# easyeda.net
KiCad netlist of a schematic drawn in EasyEDA
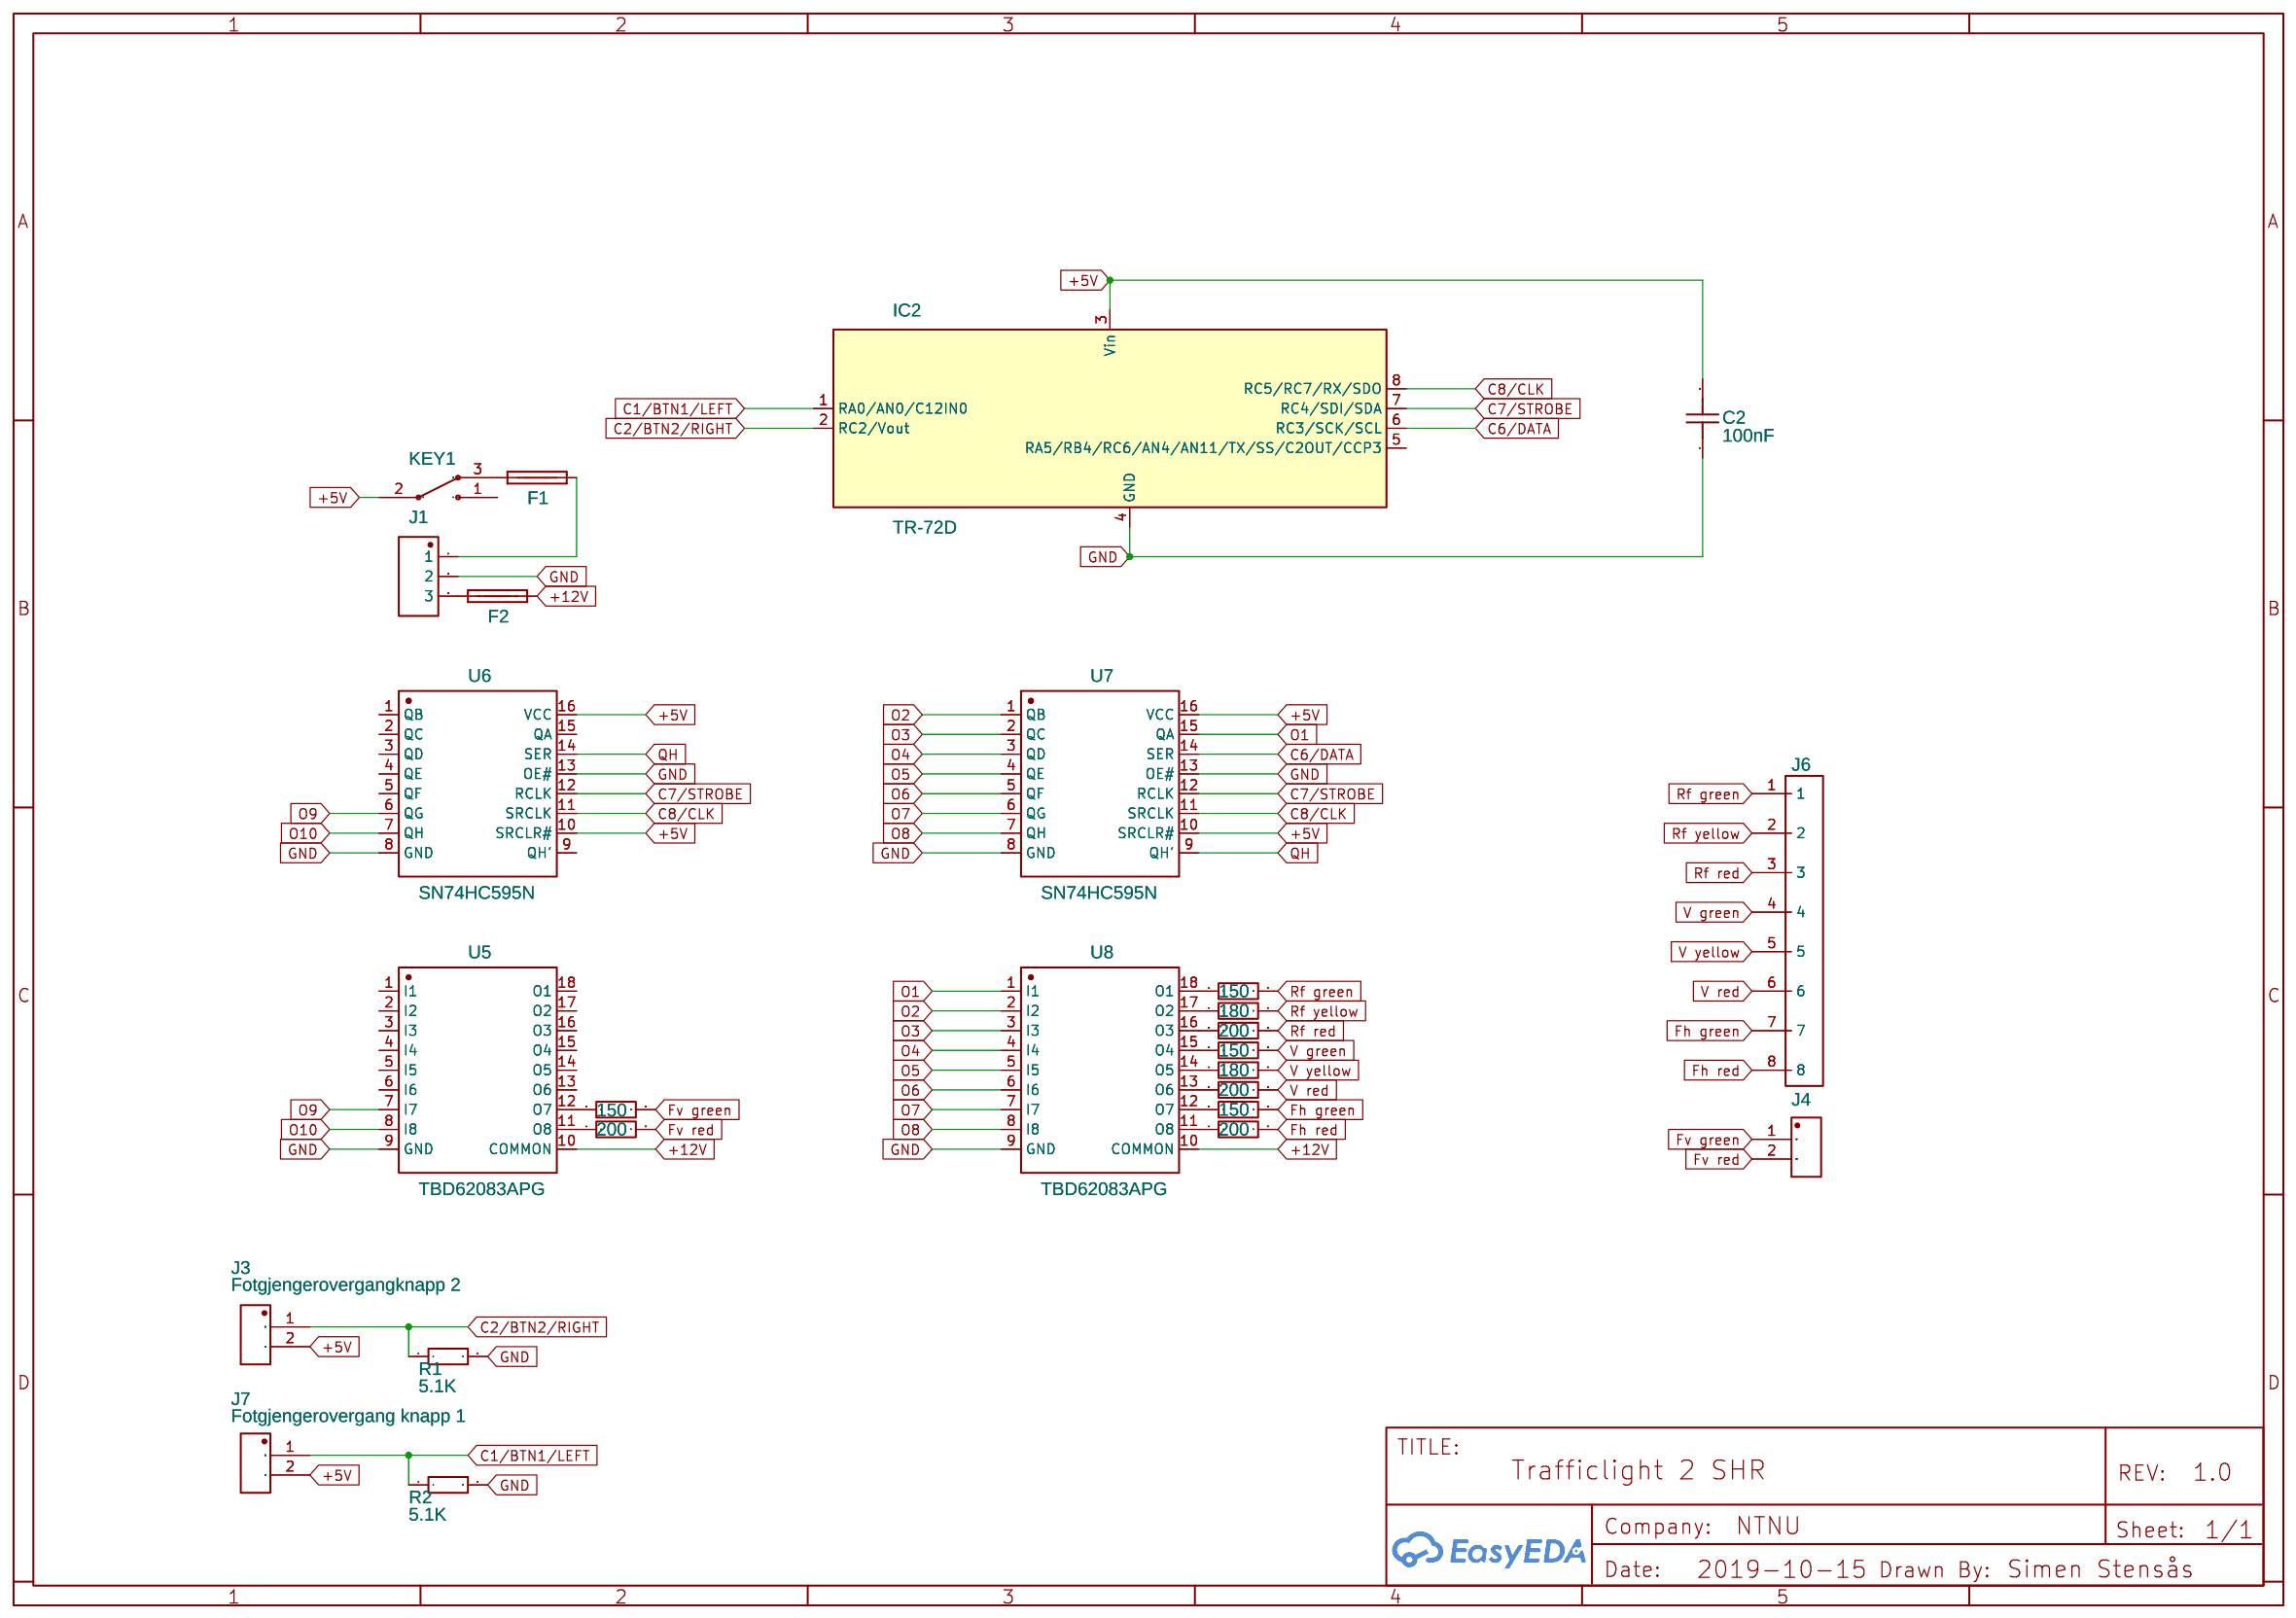
[diagram p0: schematic sheet]

(export (version "E")
  (design (tool "Eeschema 10.0.6"))
  (components
    (comp (ref "C2")
      (value "100nF")
      (fields
        (field (name "BOM_Manufacturer Part") "1210B106K100CT")
        (field (name "BOM_Supplier Part") "C304011")
      )
      (libsource (lib "") (part "1210B106K100CT"))
    )
    (comp (ref "F1")
      (value "NO")
      (fields
        (field (name "BOM_Manufacturer Part") "3403.0015.11")
        (field (name "BOM_Supplier Part") "693-3403.0015.11")
      )
      (libsource (lib "") (part "Unknown_270_225"))
    )
    (comp (ref "F2")
      (value "NO")
      (fields
        (field (name "BOM_Manufacturer Part") "3403.0015.11")
        (field (name "BOM_Supplier Part") "693-3403.0015.11")
      )
      (libsource (lib "") (part "Unknown_250_285"))
    )
    (comp (ref "IC2") (value "TR-72D") (libsource (lib "") (part "Unknown_415_200")))
    (comp (ref "J1") (value "KF127_3P_5.08") (libsource (lib "") (part "Unknown_205_285")))
    (comp (ref "J3")
      (value "Fotgjengerovergangknapp 2")
      (fields (field (name "BOM_Manufacturer Part") "KF127L-5.08"))
      (libsource (lib "") (part "Unknown_135_670"))
    )
    (comp (ref "J4")
      (value "KF127_2P_5.08")
      (fields (field (name "BOM_Manufacturer Part") "KF127L-5.08"))
      (libsource (lib "") (part "Unknown_895_575"))
    )
    (comp (ref "J6") (value "KF127-8P") (libsource (lib "") (part "Unknown_900_455")))
    (comp (ref "J7")
      (value "Fotgjengerovergang knapp 1")
      (fields (field (name "BOM_Manufacturer Part") "KF127L-5.08"))
      (libsource (lib "") (part "Unknown_135_735"))
    )
    (comp (ref "KEY1")
      (value "MSK-11027 Toggle Switches")
      (fields (field (name "BOM_Supplier Part") "C21381"))
      (libsource (lib "") (part "Unknown_215_235"))
    )
    (comp (ref "R1")
      (value "5.1K")
      (fields
        (field (name "BOM_Manufacturer Part") "RMC12065.1K1%N")
        (field (name "BOM_Supplier Part") "C325932")
      )
      (libsource (lib "") (part "RMC12065.1K1%N"))
    )
    (comp (ref "R2")
      (value "5.1K")
      (fields
        (field (name "BOM_Manufacturer Part") "RMC12065.1K1%N")
        (field (name "BOM_Supplier Part") "C325932")
      )
      (libsource (lib "") (part "RMC12065.1K1%N"))
    )
    (comp (ref "R3")
      (value "150")
      (fields
        (field (name "BOM_Manufacturer Part") "RC1206JR-07160RL")
        (field (name "BOM_Supplier Part") "C137196")
      )
      (libsource (lib "") (part "RC1206JR-07160RL"))
    )
    (comp (ref "R4")
      (value "200")
      (fields
        (field (name "BOM_Manufacturer Part") "QR1206J200RP05")
        (field (name "BOM_Supplier Part") "C149886")
      )
      (libsource (lib "") (part "QR1206J200RP05"))
    )
    (comp (ref "R5")
      (value "200")
      (fields
        (field (name "BOM_Manufacturer Part") "QR1206J200RP05")
        (field (name "BOM_Supplier Part") "C149886")
      )
      (libsource (lib "") (part "QR1206J200RP05"))
    )
    (comp (ref "R6")
      (value "200")
      (fields
        (field (name "BOM_Manufacturer Part") "QR1206J200RP05")
        (field (name "BOM_Supplier Part") "C149886")
      )
      (libsource (lib "") (part "QR1206J200RP05"))
    )
    (comp (ref "R7")
      (value "200")
      (fields
        (field (name "BOM_Manufacturer Part") "QR1206J200RP05")
        (field (name "BOM_Supplier Part") "C149886")
      )
      (libsource (lib "") (part "QR1206J200RP05"))
    )
    (comp (ref "R16")
      (value "180")
      (fields
        (field (name "BOM_Manufacturer Part") "CR1206-FX-1800ELF")
        (field (name "BOM_Supplier Part") "C204708")
      )
      (libsource (lib "") (part "CR1206-FX-1800ELF"))
    )
    (comp (ref "R17")
      (value "180")
      (fields
        (field (name "BOM_Manufacturer Part") "CR1206-FX-1800ELF")
        (field (name "BOM_Supplier Part") "C204708")
      )
      (libsource (lib "") (part "CR1206-FX-1800ELF"))
    )
    (comp (ref "R18")
      (value "150")
      (fields
        (field (name "BOM_Manufacturer Part") "RC1206JR-07160RL")
        (field (name "BOM_Supplier Part") "C137196")
      )
      (libsource (lib "") (part "RC1206JR-07160RL"))
    )
    (comp (ref "R19")
      (value "150")
      (fields
        (field (name "BOM_Manufacturer Part") "RC1206JR-07160RL")
        (field (name "BOM_Supplier Part") "C137196")
      )
      (libsource (lib "") (part "RC1206JR-07160RL"))
    )
    (comp (ref "R20")
      (value "150")
      (fields
        (field (name "BOM_Manufacturer Part") "RC1206JR-07160RL")
        (field (name "BOM_Supplier Part") "C137196")
      )
      (libsource (lib "") (part "RC1206JR-07160RL"))
    )
    (comp (ref "U5")
      (value "TBD62083APG")
      (fields (field (name "BOM_Supplier Part") "C114143"))
      (libsource (lib "") (part "Unknown_235_535"))
    )
    (comp (ref "U6")
      (value "SN74HC595N")
      (fields (field (name "BOM_Supplier Part") "C78711"))
      (libsource (lib "") (part "Unknown_235_390"))
    )
    (comp (ref "U7")
      (value "SN74HC595N")
      (fields (field (name "BOM_Supplier Part") "C78711"))
      (libsource (lib "") (part "Unknown_550_390"))
    )
    (comp (ref "U8")
      (value "TBD62083APG")
      (fields (field (name "BOM_Supplier Part") "C114143"))
      (libsource (lib "") (part "Unknown_550_535"))
    )
  )
  (nets
    (net (code "1") (name "+5V") (class "Default")
      (node (ref "C2") (pin "2") (pinfunction "2_2") (pintype "unspecified"))
      (node (ref "IC2") (pin "3") (pinfunction "Vin_3") (pintype "bidirectional"))
      (node (ref "J3") (pin "2") (pinfunction "PIN2_2") (pintype "unspecified"))
      (node (ref "J7") (pin "2") (pinfunction "PIN2_2") (pintype "unspecified"))
      (node (ref "KEY1") (pin "2") (pinfunction "2_2") (pintype "unspecified"))
      (node (ref "U6") (pin "10") (pinfunction "SRCLR#_10") (pintype "unspecified"))
      (node (ref "U6") (pin "16") (pinfunction "VCC_16") (pintype "unspecified"))
      (node (ref "U7") (pin "10") (pinfunction "SRCLR#_10") (pintype "unspecified"))
      (node (ref "U7") (pin "16") (pinfunction "VCC_16") (pintype "unspecified"))
    )
    (net (code "2") (name "+12V") (class "Default")
      (node (ref "F2") (pin "2") (pinfunction "2_2") (pintype "bidirectional"))
      (node (ref "U5") (pin "10") (pinfunction "COMMON_10") (pintype "unspecified"))
      (node (ref "U8") (pin "10") (pinfunction "COMMON_10") (pintype "unspecified"))
    )
    (net (code "3") (name "C1{slash}BTN1{slash}LEFT") (class "Default")
      (node (ref "IC2") (pin "1") (pinfunction "RA0/AN0/C12IN0_1") (pintype "bidirectional"))
      (node (ref "J7") (pin "1") (pinfunction "PIN1_1") (pintype "unspecified"))
      (node (ref "R2") (pin "1") (pinfunction "1_1") (pintype "unspecified"))
    )
    (net (code "4") (name "C2{slash}BTN2{slash}RIGHT") (class "Default")
      (node (ref "IC2") (pin "2") (pinfunction "RC2/Vout_2") (pintype "bidirectional"))
      (node (ref "J3") (pin "1") (pinfunction "PIN1_1") (pintype "unspecified"))
      (node (ref "R1") (pin "1") (pinfunction "1_1") (pintype "unspecified"))
    )
    (net (code "5") (name "C6{slash}DATA") (class "Default")
      (node (ref "IC2") (pin "6") (pinfunction "RC3/SCK/SCL_6") (pintype "bidirectional"))
      (node (ref "U7") (pin "14") (pinfunction "SER_14") (pintype "unspecified"))
    )
    (net (code "6") (name "C7{slash}STROBE") (class "Default")
      (node (ref "IC2") (pin "7") (pinfunction "RC4/SDI/SDA_7") (pintype "bidirectional"))
      (node (ref "U6") (pin "12") (pinfunction "RCLK_12") (pintype "unspecified"))
      (node (ref "U7") (pin "12") (pinfunction "RCLK_12") (pintype "unspecified"))
    )
    (net (code "7") (name "C8{slash}CLK") (class "Default")
      (node (ref "IC2") (pin "8") (pinfunction "RC5/RC7/RX/SDO_8") (pintype "bidirectional"))
      (node (ref "U6") (pin "11") (pinfunction "SRCLK_11") (pintype "unspecified"))
      (node (ref "U7") (pin "11") (pinfunction "SRCLK_11") (pintype "unspecified"))
    )
    (net (code "8") (name "Fh green") (class "Default")
      (node (ref "J6") (pin "7") (pinfunction "7_7") (pintype "unspecified"))
      (node (ref "R18") (pin "2") (pinfunction "2_2") (pintype "input"))
    )
    (net (code "9") (name "Fh red") (class "Default")
      (node (ref "J6") (pin "8") (pinfunction "8_8") (pintype "unspecified"))
      (node (ref "R5") (pin "2") (pinfunction "2_2") (pintype "unspecified"))
    )
    (net (code "10") (name "Fv green") (class "Default")
      (node (ref "J4") (pin "1") (pinfunction "PIN1_1") (pintype "unspecified"))
      (node (ref "R3") (pin "2") (pinfunction "2_2") (pintype "input"))
    )
    (net (code "11") (name "Fv red") (class "Default")
      (node (ref "J4") (pin "2") (pinfunction "PIN2_2") (pintype "unspecified"))
      (node (ref "R4") (pin "2") (pinfunction "2_2") (pintype "unspecified"))
    )
    (net (code "12") (name "GND") (class "Default")
      (node (ref "C2") (pin "1") (pinfunction "1_1") (pintype "unspecified"))
      (node (ref "IC2") (pin "4") (pinfunction "GND_4") (pintype "bidirectional"))
      (node (ref "J1") (pin "2") (pinfunction "2_2") (pintype "input"))
      (node (ref "R1") (pin "2") (pinfunction "2_2") (pintype "unspecified"))
      (node (ref "R2") (pin "2") (pinfunction "2_2") (pintype "unspecified"))
      (node (ref "U5") (pin "9") (pinfunction "GND_9") (pintype "unspecified"))
      (node (ref "U6") (pin "13") (pinfunction "OE#_13") (pintype "unspecified"))
      (node (ref "U6") (pin "8") (pinfunction "GND_8") (pintype "unspecified"))
      (node (ref "U7") (pin "13") (pinfunction "OE#_13") (pintype "unspecified"))
      (node (ref "U7") (pin "8") (pinfunction "GND_8") (pintype "unspecified"))
      (node (ref "U8") (pin "9") (pinfunction "GND_9") (pintype "unspecified"))
    )
    (net (code "13") (name "Net-(F1-Pad1)") (class "Default")
      (node (ref "F1") (pin "1") (pinfunction "1_1") (pintype "bidirectional"))
      (node (ref "KEY1") (pin "3") (pinfunction "3_3") (pintype "unspecified"))
    )
    (net (code "14") (name "Net-(F1-Pad2)") (class "Default")
      (node (ref "F1") (pin "2") (pinfunction "2_2") (pintype "bidirectional"))
      (node (ref "J1") (pin "1") (pinfunction "1_1") (pintype "input"))
    )
    (net (code "15") (name "Net-(F2-Pad1)") (class "Default")
      (node (ref "F2") (pin "1") (pinfunction "1_1") (pintype "bidirectional"))
      (node (ref "J1") (pin "3") (pinfunction "3_3") (pintype "input"))
    )
    (net (code "16") (name "Net-(U5-O7)") (class "Default")
      (node (ref "R3") (pin "1") (pinfunction "1_1") (pintype "input"))
      (node (ref "U5") (pin "12") (pinfunction "O7_12") (pintype "unspecified"))
    )
    (net (code "17") (name "Net-(U5-O8)") (class "Default")
      (node (ref "R4") (pin "1") (pinfunction "1_1") (pintype "unspecified"))
      (node (ref "U5") (pin "11") (pinfunction "O8_11") (pintype "unspecified"))
    )
    (net (code "18") (name "Net-(U8-O1)") (class "Default")
      (node (ref "R20") (pin "1") (pinfunction "1_1") (pintype "input"))
      (node (ref "U8") (pin "18") (pinfunction "O1_18") (pintype "unspecified"))
    )
    (net (code "19") (name "Net-(U8-O2)") (class "Default")
      (node (ref "R17") (pin "1") (pinfunction "1_1") (pintype "unspecified"))
      (node (ref "U8") (pin "17") (pinfunction "O2_17") (pintype "unspecified"))
    )
    (net (code "20") (name "Net-(U8-O3)") (class "Default")
      (node (ref "R7") (pin "1") (pinfunction "1_1") (pintype "unspecified"))
      (node (ref "U8") (pin "16") (pinfunction "O3_16") (pintype "unspecified"))
    )
    (net (code "21") (name "Net-(U8-O4)") (class "Default")
      (node (ref "R19") (pin "1") (pinfunction "1_1") (pintype "input"))
      (node (ref "U8") (pin "15") (pinfunction "O4_15") (pintype "unspecified"))
    )
    (net (code "22") (name "Net-(U8-O5)") (class "Default")
      (node (ref "R16") (pin "1") (pinfunction "1_1") (pintype "unspecified"))
      (node (ref "U8") (pin "14") (pinfunction "O5_14") (pintype "unspecified"))
    )
    (net (code "23") (name "Net-(U8-O6)") (class "Default")
      (node (ref "R6") (pin "1") (pinfunction "1_1") (pintype "unspecified"))
      (node (ref "U8") (pin "13") (pinfunction "O6_13") (pintype "unspecified"))
    )
    (net (code "24") (name "Net-(U8-O7)") (class "Default")
      (node (ref "R18") (pin "1") (pinfunction "1_1") (pintype "input"))
      (node (ref "U8") (pin "12") (pinfunction "O7_12") (pintype "unspecified"))
    )
    (net (code "25") (name "Net-(U8-O8)") (class "Default")
      (node (ref "R5") (pin "1") (pinfunction "1_1") (pintype "unspecified"))
      (node (ref "U8") (pin "11") (pinfunction "O8_11") (pintype "unspecified"))
    )
    (net (code "26") (name "O1") (class "Default")
      (node (ref "U7") (pin "15") (pinfunction "QA_15") (pintype "unspecified"))
      (node (ref "U8") (pin "1") (pinfunction "I1_1") (pintype "unspecified"))
    )
    (net (code "27") (name "O2") (class "Default")
      (node (ref "U7") (pin "1") (pinfunction "QB_1") (pintype "unspecified"))
      (node (ref "U8") (pin "2") (pinfunction "I2_2") (pintype "unspecified"))
    )
    (net (code "28") (name "O3") (class "Default")
      (node (ref "U7") (pin "2") (pinfunction "QC_2") (pintype "unspecified"))
      (node (ref "U8") (pin "3") (pinfunction "I3_3") (pintype "unspecified"))
    )
    (net (code "29") (name "O4") (class "Default")
      (node (ref "U7") (pin "3") (pinfunction "QD_3") (pintype "unspecified"))
      (node (ref "U8") (pin "4") (pinfunction "I4_4") (pintype "unspecified"))
    )
    (net (code "30") (name "O5") (class "Default")
      (node (ref "U7") (pin "4") (pinfunction "QE_4") (pintype "unspecified"))
      (node (ref "U8") (pin "5") (pinfunction "I5_5") (pintype "unspecified"))
    )
    (net (code "31") (name "O6") (class "Default")
      (node (ref "U7") (pin "5") (pinfunction "QF_5") (pintype "unspecified"))
      (node (ref "U8") (pin "6") (pinfunction "I6_6") (pintype "unspecified"))
    )
    (net (code "32") (name "O7") (class "Default")
      (node (ref "U7") (pin "6") (pinfunction "QG_6") (pintype "unspecified"))
      (node (ref "U8") (pin "7") (pinfunction "I7_7") (pintype "unspecified"))
    )
    (net (code "33") (name "O8") (class "Default")
      (node (ref "U7") (pin "7") (pinfunction "QH_7") (pintype "unspecified"))
      (node (ref "U8") (pin "8") (pinfunction "I8_8") (pintype "unspecified"))
    )
    (net (code "34") (name "O9") (class "Default")
      (node (ref "U5") (pin "7") (pinfunction "I7_7") (pintype "unspecified"))
      (node (ref "U6") (pin "6") (pinfunction "QG_6") (pintype "unspecified"))
    )
    (net (code "35") (name "O10") (class "Default")
      (node (ref "U5") (pin "8") (pinfunction "I8_8") (pintype "unspecified"))
      (node (ref "U6") (pin "7") (pinfunction "QH_7") (pintype "unspecified"))
    )
    (net (code "36") (name "QH") (class "Default")
      (node (ref "U6") (pin "14") (pinfunction "SER_14") (pintype "unspecified"))
      (node (ref "U7") (pin "9") (pinfunction "QH'_9") (pintype "unspecified"))
    )
    (net (code "37") (name "Rf green") (class "Default")
      (node (ref "J6") (pin "1") (pinfunction "1_1") (pintype "unspecified"))
      (node (ref "R20") (pin "2") (pinfunction "2_2") (pintype "input"))
    )
    (net (code "38") (name "Rf red") (class "Default")
      (node (ref "J6") (pin "3") (pinfunction "3_3") (pintype "unspecified"))
      (node (ref "R7") (pin "2") (pinfunction "2_2") (pintype "unspecified"))
    )
    (net (code "39") (name "Rf yellow") (class "Default")
      (node (ref "J6") (pin "2") (pinfunction "2_2") (pintype "unspecified"))
      (node (ref "R17") (pin "2") (pinfunction "2_2") (pintype "unspecified"))
    )
    (net (code "40") (name "V green") (class "Default")
      (node (ref "J6") (pin "4") (pinfunction "4_4") (pintype "unspecified"))
      (node (ref "R19") (pin "2") (pinfunction "2_2") (pintype "input"))
    )
    (net (code "41") (name "V red") (class "Default")
      (node (ref "J6") (pin "6") (pinfunction "6_6") (pintype "unspecified"))
      (node (ref "R6") (pin "2") (pinfunction "2_2") (pintype "unspecified"))
    )
    (net (code "42") (name "V yellow") (class "Default")
      (node (ref "J6") (pin "5") (pinfunction "5_5") (pintype "unspecified"))
      (node (ref "R16") (pin "2") (pinfunction "2_2") (pintype "unspecified"))
    )
    (net (code "43") (name "unconnected-(IC2-RA5{slash}RB4{slash}RC6{slash}AN4{slash}AN11{slash}TX{slash}SS{slash}C2OUT{slash}CCP3-Pad5)") (class "Default")
      (node (ref "IC2") (pin "5") (pinfunction "RA5/RB4/RC6/AN4/AN11/TX/SS/C2OUT/CCP3_5") (pintype "bidirectional"))
    )
    (net (code "44") (name "unconnected-(KEY1-Pad1)") (class "Default")
      (node (ref "KEY1") (pin "1") (pinfunction "1_1") (pintype "unspecified"))
    )
    (net (code "45") (name "unconnected-(U5-I1-Pad1)") (class "Default")
      (node (ref "U5") (pin "1") (pinfunction "I1_1") (pintype "unspecified"))
    )
    (net (code "46") (name "unconnected-(U5-I2-Pad2)") (class "Default")
      (node (ref "U5") (pin "2") (pinfunction "I2_2") (pintype "unspecified"))
    )
    (net (code "47") (name "unconnected-(U5-I3-Pad3)") (class "Default")
      (node (ref "U5") (pin "3") (pinfunction "I3_3") (pintype "unspecified"))
    )
    (net (code "48") (name "unconnected-(U5-I4-Pad4)") (class "Default")
      (node (ref "U5") (pin "4") (pinfunction "I4_4") (pintype "unspecified"))
    )
    (net (code "49") (name "unconnected-(U5-I5-Pad5)") (class "Default")
      (node (ref "U5") (pin "5") (pinfunction "I5_5") (pintype "unspecified"))
    )
    (net (code "50") (name "unconnected-(U5-I6-Pad6)") (class "Default")
      (node (ref "U5") (pin "6") (pinfunction "I6_6") (pintype "unspecified"))
    )
    (net (code "51") (name "unconnected-(U5-O1-Pad18)") (class "Default")
      (node (ref "U5") (pin "18") (pinfunction "O1_18") (pintype "unspecified"))
    )
    (net (code "52") (name "unconnected-(U5-O2-Pad17)") (class "Default")
      (node (ref "U5") (pin "17") (pinfunction "O2_17") (pintype "unspecified"))
    )
    (net (code "53") (name "unconnected-(U5-O3-Pad16)") (class "Default")
      (node (ref "U5") (pin "16") (pinfunction "O3_16") (pintype "unspecified"))
    )
    (net (code "54") (name "unconnected-(U5-O4-Pad15)") (class "Default")
      (node (ref "U5") (pin "15") (pinfunction "O4_15") (pintype "unspecified"))
    )
    (net (code "55") (name "unconnected-(U5-O5-Pad14)") (class "Default")
      (node (ref "U5") (pin "14") (pinfunction "O5_14") (pintype "unspecified"))
    )
    (net (code "56") (name "unconnected-(U5-O6-Pad13)") (class "Default")
      (node (ref "U5") (pin "13") (pinfunction "O6_13") (pintype "unspecified"))
    )
    (net (code "57") (name "unconnected-(U6-QA-Pad15)") (class "Default")
      (node (ref "U6") (pin "15") (pinfunction "QA_15") (pintype "unspecified"))
    )
    (net (code "58") (name "unconnected-(U6-QB-Pad1)") (class "Default")
      (node (ref "U6") (pin "1") (pinfunction "QB_1") (pintype "unspecified"))
    )
    (net (code "59") (name "unconnected-(U6-QC-Pad2)") (class "Default")
      (node (ref "U6") (pin "2") (pinfunction "QC_2") (pintype "unspecified"))
    )
    (net (code "60") (name "unconnected-(U6-QD-Pad3)") (class "Default")
      (node (ref "U6") (pin "3") (pinfunction "QD_3") (pintype "unspecified"))
    )
    (net (code "61") (name "unconnected-(U6-QE-Pad4)") (class "Default")
      (node (ref "U6") (pin "4") (pinfunction "QE_4") (pintype "unspecified"))
    )
    (net (code "62") (name "unconnected-(U6-QF-Pad5)") (class "Default")
      (node (ref "U6") (pin "5") (pinfunction "QF_5") (pintype "unspecified"))
    )
    (net (code "63") (name "unconnected-(U6-QH'-Pad9)") (class "Default")
      (node (ref "U6") (pin "9") (pinfunction "QH'_9") (pintype "unspecified"))
    )
  )
)
